# awc_v1.net
KiCad netlist of a schematic drawn in EAGLE
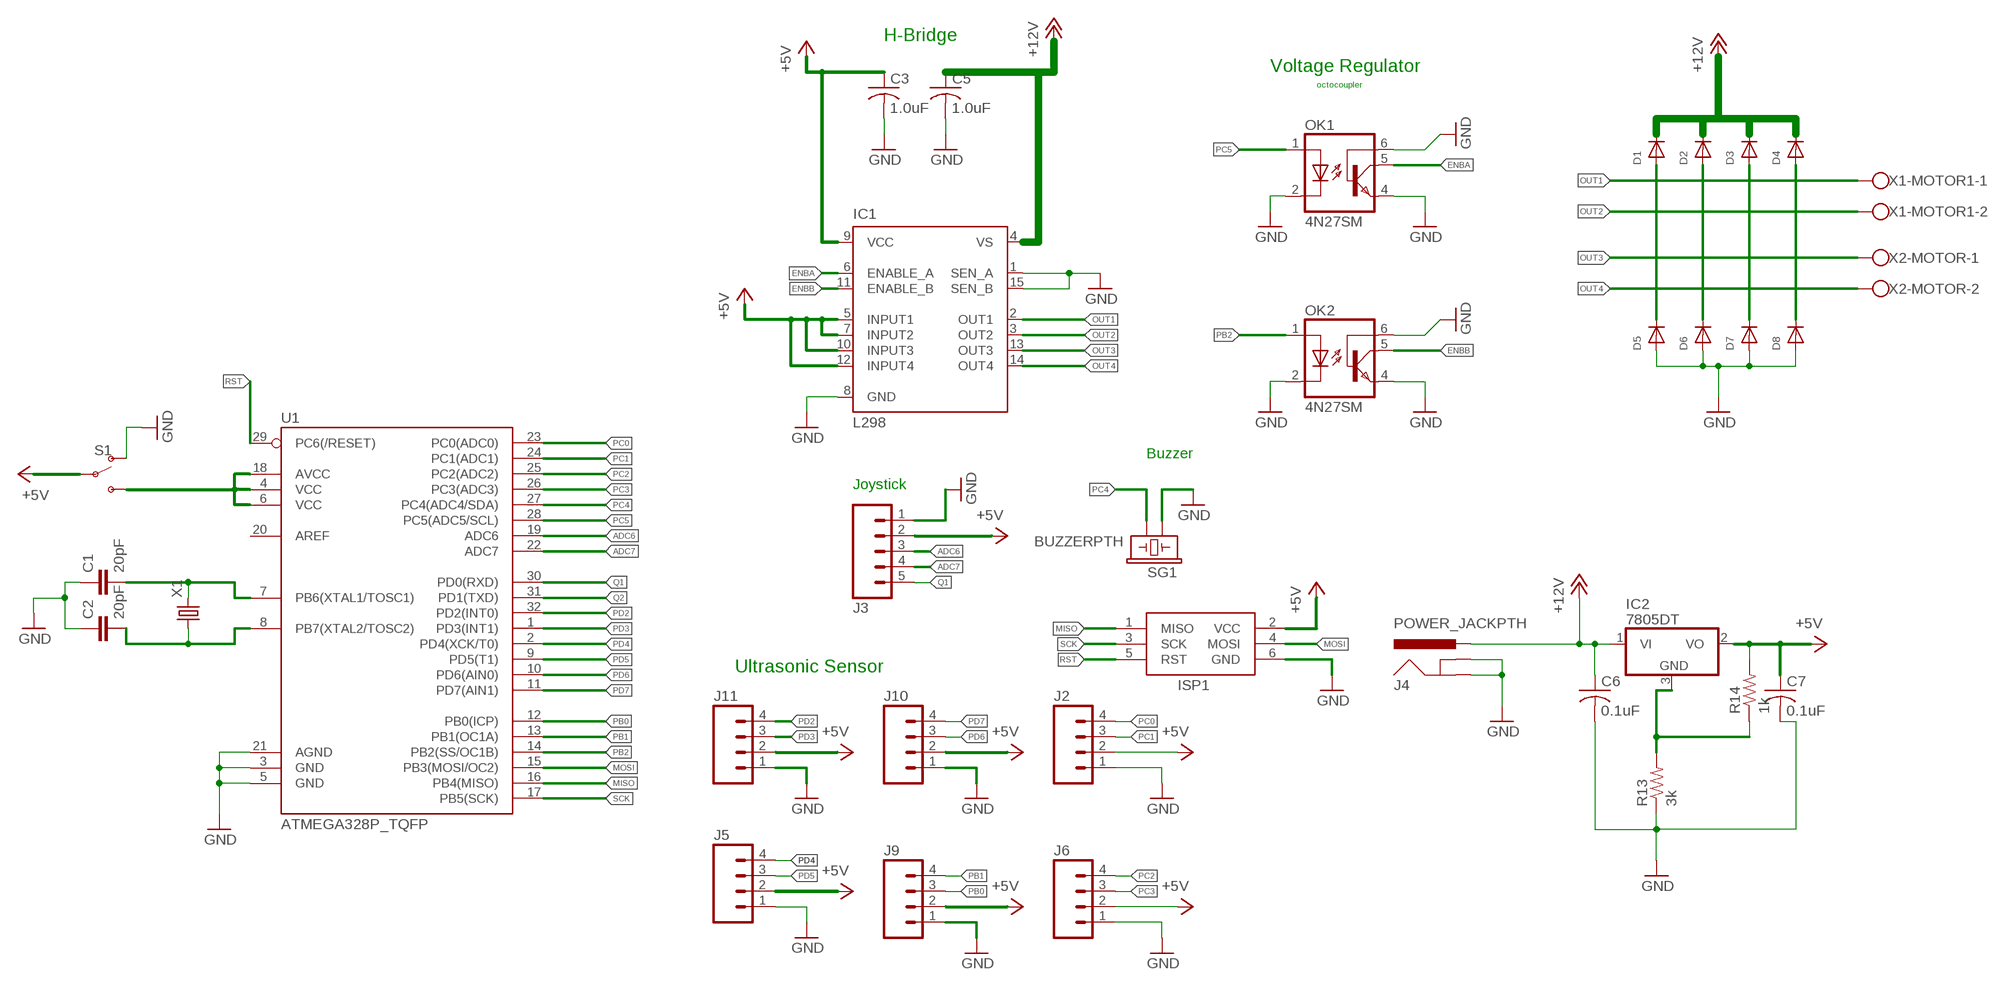
[diagram p0: schematic, sheet 1]

(export (version "E")
  (design (tool "Eeschema 10.0.6"))
  (components
    (comp (ref "C1")
      (value "20pF")
      (footprint "eagle-import:C0805")
      (libsource (lib "eagle-import") (part "C-EUC0805"))
    )
    (comp (ref "C2")
      (value "20pF")
      (footprint "eagle-import:C0805")
      (libsource (lib "eagle-import") (part "C-EUC0805"))
    )
    (comp (ref "C3")
      (value "1.0uF")
      (footprint "eagle-import:C0805")
      (libsource (lib "eagle-import") (part "C-USC0805"))
    )
    (comp (ref "C5")
      (value "1.0uF")
      (footprint "eagle-import:C0805")
      (libsource (lib "eagle-import") (part "C-USC0805"))
    )
    (comp (ref "C6")
      (value "0.1uF")
      (footprint "eagle-import:C0805")
      (libsource (lib "eagle-import") (part "C-USC0805"))
    )
    (comp (ref "C7")
      (value "0.1uF")
      (footprint "eagle-import:C0805")
      (libsource (lib "eagle-import") (part "C-USC0805"))
    )
    (comp (ref "D1")
      (value "DIODESOD-523")
      (footprint "eagle-import:SOD-523")
      (libsource (lib "eagle-import") (part "DIODESOD-523"))
    )
    (comp (ref "D2")
      (value "DIODESOD-523")
      (footprint "eagle-import:SOD-523")
      (libsource (lib "eagle-import") (part "DIODESOD-523"))
    )
    (comp (ref "D3")
      (value "DIODESOD-523")
      (footprint "eagle-import:SOD-523")
      (libsource (lib "eagle-import") (part "DIODESOD-523"))
    )
    (comp (ref "D4")
      (value "DIODESOD-523")
      (footprint "eagle-import:SOD-523")
      (libsource (lib "eagle-import") (part "DIODESOD-523"))
    )
    (comp (ref "D5")
      (value "DIODESOD-523")
      (footprint "eagle-import:SOD-523")
      (libsource (lib "eagle-import") (part "DIODESOD-523"))
    )
    (comp (ref "D6")
      (value "DIODESOD-523")
      (footprint "eagle-import:SOD-523")
      (libsource (lib "eagle-import") (part "DIODESOD-523"))
    )
    (comp (ref "D7")
      (value "DIODESOD-523")
      (footprint "eagle-import:SOD-523")
      (libsource (lib "eagle-import") (part "DIODESOD-523"))
    )
    (comp (ref "D8")
      (value "DIODESOD-523")
      (footprint "eagle-import:SOD-523")
      (libsource (lib "eagle-import") (part "DIODESOD-523"))
    )
    (comp (ref "IC1")
      (value "L298")
      (footprint "eagle-import:MULTIWATT-15")
      (fields (field (name "MPN") "L298N"))
      (libsource (lib "eagle-import") (part "L298"))
    )
    (comp (ref "IC2")
      (value "7805DT")
      (footprint "eagle-import:TO252")
      (libsource (lib "eagle-import") (part "78DT05"))
    )
    (comp (ref "ISP1")
      (value "AVRISP-6")
      (footprint "eagle-import:AVRISP")
      (libsource (lib "eagle-import") (part "AVRISP-6"))
    )
    (comp (ref "J2")
      (value "M04SCREW_LOCK")
      (footprint "eagle-import:SCREWTERMINAL-3.5MM-4_LOCK")
      (libsource (lib "eagle-import") (part "M04SCREW_LOCK"))
    )
    (comp (ref "J3")
      (value "M05SCREW")
      (footprint "eagle-import:SCREWTERMINAL-3.5MM-5")
      (libsource (lib "eagle-import") (part "M05SCREW"))
    )
    (comp (ref "J4")
      (value "POWER_JACKPTH")
      (footprint "eagle-import:POWER_JACK_PTH")
      (libsource (lib "eagle-import") (part "POWER_JACKPTH"))
    )
    (comp (ref "J5")
      (value "M04SCREW_LOCK")
      (footprint "eagle-import:SCREWTERMINAL-3.5MM-4_LOCK")
      (libsource (lib "eagle-import") (part "M04SCREW_LOCK"))
    )
    (comp (ref "J6")
      (value "M04SCREW_LOCK")
      (footprint "eagle-import:SCREWTERMINAL-3.5MM-4_LOCK")
      (libsource (lib "eagle-import") (part "M04SCREW_LOCK"))
    )
    (comp (ref "J9")
      (value "M04SCREW_LOCK")
      (footprint "eagle-import:SCREWTERMINAL-3.5MM-4_LOCK")
      (libsource (lib "eagle-import") (part "M04SCREW_LOCK"))
    )
    (comp (ref "J10")
      (value "M04SCREW_LOCK")
      (footprint "eagle-import:SCREWTERMINAL-3.5MM-4_LOCK")
      (libsource (lib "eagle-import") (part "M04SCREW_LOCK"))
    )
    (comp (ref "J11")
      (value "M04SCREW_LOCK")
      (footprint "eagle-import:SCREWTERMINAL-3.5MM-4_LOCK")
      (libsource (lib "eagle-import") (part "M04SCREW_LOCK"))
    )
    (comp (ref "OK1")
      (value "4N27SM")
      (footprint "eagle-import:DIL6-SMD")
      (fields (field (name "MF") "FAIRCHILD SEMICONDUCTOR") (field (name "MPN") "4N27S-M"))
      (libsource (lib "eagle-import") (part "4N?MS27"))
    )
    (comp (ref "OK2")
      (value "4N27SM")
      (footprint "eagle-import:DIL6-SMD")
      (fields (field (name "MF") "FAIRCHILD SEMICONDUCTOR") (field (name "MPN") "4N27S-M"))
      (libsource (lib "eagle-import") (part "4N?MS27"))
    )
    (comp (ref "R13")
      (value "3k")
      (footprint "eagle-import:0402-RES")
      (libsource (lib "eagle-import") (part "RESISTOR0402"))
    )
    (comp (ref "R14")
      (value "1k")
      (footprint "eagle-import:M0805")
      (libsource (lib "eagle-import") (part "R-US_M0805"))
    )
    (comp (ref "S1")
      (value "SWITCH-SPDT-PTH-11.6X4.0MM")
      (footprint "eagle-import:SWITCH_SPDT_PTH_11.6X4.0MM")
      (libsource (lib "eagle-import") (part "SWITCH-SPDT-PTH-11.6X4.0MM"))
    )
    (comp (ref "SG1")
      (value "BUZZERPTH")
      (footprint "eagle-import:BUZZER-12MM")
      (libsource (lib "eagle-import") (part "BUZZERPTH"))
    )
    (comp (ref "U1")
      (value "ATMEGA328P_TQFP")
      (footprint "eagle-import:TQFP32-08")
      (libsource (lib "eagle-import") (part "ATMEGA328P_TQFP"))
    )
    (comp (ref "X1")
      (value "CRYSTALHC49UP")
      (footprint "eagle-import:HC49UP")
      (libsource (lib "eagle-import") (part "CRYSTALHC49UP"))
    )
    (comp (ref "X1-MOTOR1")
      (value "W237-102")
      (footprint "eagle-import:W237-102")
      (fields (field (name "MPN") "237-102"))
      (libsource (lib "eagle-import") (part "W237-102"))
    )
    (comp (ref "X2-MOTOR")
      (value "W237-102")
      (footprint "eagle-import:W237-102")
      (fields (field (name "MPN") "237-102"))
      (libsource (lib "eagle-import") (part "W237-102"))
    )
  )
  (nets
    (net (code "1") (name "+5V") (class "Default")
      (node (ref "C3") (pin "1") (pinfunction "1_1") (pintype "passive"))
      (node (ref "C7") (pin "1") (pinfunction "1_1") (pintype "passive"))
      (node (ref "IC1") (pin "10") (pinfunction "INPUT3_10") (pintype "input"))
      (node (ref "IC1") (pin "12") (pinfunction "INPUT4_12") (pintype "input"))
      (node (ref "IC1") (pin "5") (pinfunction "INPUT1_5") (pintype "input"))
      (node (ref "IC1") (pin "7") (pinfunction "INPUT2_7") (pintype "input"))
      (node (ref "IC1") (pin "9") (pinfunction "VCC_9") (pintype "power_in"))
      (node (ref "IC2") (pin "2") (pinfunction "VO_2") (pintype "passive"))
      (node (ref "ISP1") (pin "2") (pinfunction "VCC_2") (pintype "power_in"))
      (node (ref "J10") (pin "2") (pinfunction "2_2") (pintype "passive"))
      (node (ref "J11") (pin "2") (pinfunction "2_2") (pintype "passive"))
      (node (ref "J2") (pin "2") (pinfunction "2_2") (pintype "passive"))
      (node (ref "J3") (pin "2") (pinfunction "2_2") (pintype "passive"))
      (node (ref "J5") (pin "2") (pinfunction "2_2") (pintype "passive"))
      (node (ref "J6") (pin "2") (pinfunction "2_2") (pintype "passive"))
      (node (ref "J9") (pin "2") (pinfunction "2_2") (pintype "passive"))
      (node (ref "R14") (pin "2") (pinfunction "2_2") (pintype "passive"))
      (node (ref "S1") (pin "2") (pinfunction "P_2") (pintype "passive"))
    )
    (net (code "2") (name "+12V") (class "Default")
      (node (ref "C5") (pin "1") (pinfunction "1_1") (pintype "passive"))
      (node (ref "C6") (pin "1") (pinfunction "1_1") (pintype "passive"))
      (node (ref "D1") (pin "K") (pinfunction "C_K") (pintype "passive"))
      (node (ref "D2") (pin "K") (pinfunction "C_K") (pintype "passive"))
      (node (ref "D3") (pin "K") (pinfunction "C_K") (pintype "passive"))
      (node (ref "D4") (pin "K") (pinfunction "C_K") (pintype "passive"))
      (node (ref "IC1") (pin "4") (pinfunction "VS_4") (pintype "power_in"))
      (node (ref "IC2") (pin "1") (pinfunction "VI_1") (pintype "input"))
      (node (ref "J4") (pin "PWR") (pinfunction "PWR_PWR") (pintype "bidirectional"))
    )
    (net (code "3") (name "ADC6") (class "Default")
      (node (ref "J3") (pin "3") (pinfunction "3_3") (pintype "passive"))
      (node (ref "U1") (pin "19") (pinfunction "ADC6_19") (pintype "bidirectional"))
    )
    (net (code "4") (name "ADC7") (class "Default")
      (node (ref "J3") (pin "4") (pinfunction "4_4") (pintype "passive"))
      (node (ref "U1") (pin "22") (pinfunction "ADC7_22") (pintype "bidirectional"))
    )
    (net (code "5") (name "ENBA") (class "Default")
      (node (ref "IC1") (pin "6") (pinfunction "ENABLE_A_6") (pintype "input"))
      (node (ref "OK1") (pin "5") (pinfunction "COL_5") (pintype "passive"))
    )
    (net (code "6") (name "ENBB") (class "Default")
      (node (ref "IC1") (pin "11") (pinfunction "ENABLE_B_11") (pintype "input"))
      (node (ref "OK2") (pin "5") (pinfunction "COL_5") (pintype "passive"))
    )
    (net (code "7") (name "GND") (class "Default")
      (node (ref "C1") (pin "1") (pinfunction "1_1") (pintype "passive"))
      (node (ref "C2") (pin "1") (pinfunction "1_1") (pintype "passive"))
      (node (ref "C3") (pin "2") (pinfunction "2_2") (pintype "passive"))
      (node (ref "C5") (pin "2") (pinfunction "2_2") (pintype "passive"))
      (node (ref "C6") (pin "2") (pinfunction "2_2") (pintype "passive"))
      (node (ref "C7") (pin "2") (pinfunction "2_2") (pintype "passive"))
      (node (ref "D5") (pin "A") (pinfunction "A_A") (pintype "passive"))
      (node (ref "D6") (pin "A") (pinfunction "A_A") (pintype "passive"))
      (node (ref "D7") (pin "A") (pinfunction "A_A") (pintype "passive"))
      (node (ref "D8") (pin "A") (pinfunction "A_A") (pintype "passive"))
      (node (ref "IC1") (pin "1") (pinfunction "SEN_A_1") (pintype "input"))
      (node (ref "IC1") (pin "15") (pinfunction "SEN_B_15") (pintype "input"))
      (node (ref "IC1") (pin "8") (pinfunction "GND_8") (pintype "power_in"))
      (node (ref "ISP1") (pin "6") (pinfunction "GND_6") (pintype "power_in"))
      (node (ref "J10") (pin "1") (pinfunction "1_1") (pintype "passive"))
      (node (ref "J11") (pin "1") (pinfunction "1_1") (pintype "passive"))
      (node (ref "J2") (pin "1") (pinfunction "1_1") (pintype "passive"))
      (node (ref "J3") (pin "1") (pinfunction "1_1") (pintype "passive"))
      (node (ref "J4") (pin "GND") (pinfunction "GND_GND") (pintype "bidirectional"))
      (node (ref "J4") (pin "GNDBREAK") (pinfunction "GNDBREAK_GNDBREAK") (pintype "bidirectional"))
      (node (ref "J5") (pin "1") (pinfunction "1_1") (pintype "passive"))
      (node (ref "J6") (pin "1") (pinfunction "1_1") (pintype "passive"))
      (node (ref "J9") (pin "1") (pinfunction "1_1") (pintype "passive"))
      (node (ref "OK1") (pin "2") (pinfunction "C_2") (pintype "passive"))
      (node (ref "OK1") (pin "4") (pinfunction "EMI_4") (pintype "passive"))
      (node (ref "OK1") (pin "6") (pinfunction "BAS_6") (pintype "passive"))
      (node (ref "OK2") (pin "2") (pinfunction "C_2") (pintype "passive"))
      (node (ref "OK2") (pin "4") (pinfunction "EMI_4") (pintype "passive"))
      (node (ref "OK2") (pin "6") (pinfunction "BAS_6") (pintype "passive"))
      (node (ref "R13") (pin "1") (pinfunction "1_1") (pintype "passive"))
      (node (ref "S1") (pin "1") (pinfunction "O_1") (pintype "passive"))
      (node (ref "SG1") (pin "+") (pinfunction "1_+") (pintype "passive"))
      (node (ref "U1") (pin "21") (pinfunction "AGND_21") (pintype "bidirectional"))
      (node (ref "U1") (pin "3") (pinfunction "GND_3") (pintype "bidirectional"))
      (node (ref "U1") (pin "5") (pinfunction "GND_5") (pintype "bidirectional"))
    )
    (net (code "8") (name "MISO") (class "Default")
      (node (ref "ISP1") (pin "1") (pinfunction "MISO_1") (pintype "input"))
      (node (ref "U1") (pin "16") (pinfunction "PB4(MISO)_16") (pintype "bidirectional"))
    )
    (net (code "9") (name "MOSI") (class "Default")
      (node (ref "ISP1") (pin "4") (pinfunction "MOSI_4") (pintype "output"))
      (node (ref "U1") (pin "15") (pinfunction "PB3(MOSI/OC2)_15") (pintype "bidirectional"))
    )
    (net (code "10") (name "Net-(D5-C)") (class "Default")
      (node (ref "D1") (pin "A") (pinfunction "A_A") (pintype "passive"))
      (node (ref "D5") (pin "K") (pinfunction "C_K") (pintype "passive"))
    )
    (net (code "11") (name "Net-(D6-C)") (class "Default")
      (node (ref "D2") (pin "A") (pinfunction "A_A") (pintype "passive"))
      (node (ref "D6") (pin "K") (pinfunction "C_K") (pintype "passive"))
    )
    (net (code "12") (name "Net-(D7-C)") (class "Default")
      (node (ref "D3") (pin "A") (pinfunction "A_A") (pintype "passive"))
      (node (ref "D7") (pin "K") (pinfunction "C_K") (pintype "passive"))
    )
    (net (code "13") (name "Net-(D8-C)") (class "Default")
      (node (ref "D4") (pin "A") (pinfunction "A_A") (pintype "passive"))
      (node (ref "D8") (pin "K") (pinfunction "C_K") (pintype "passive"))
    )
    (net (code "14") (name "Net-(IC2-GND)") (class "Default")
      (node (ref "IC2") (pin "3") (pinfunction "GND_3") (pintype "passive"))
      (node (ref "R13") (pin "2") (pinfunction "2_2") (pintype "passive"))
      (node (ref "R14") (pin "1") (pinfunction "1_1") (pintype "passive"))
    )
    (net (code "15") (name "Net-(S1-S)") (class "Default")
      (node (ref "S1") (pin "3") (pinfunction "S_3") (pintype "passive"))
      (node (ref "U1") (pin "18") (pinfunction "AVCC_18") (pintype "bidirectional"))
      (node (ref "U1") (pin "4") (pinfunction "VCC_4") (pintype "bidirectional"))
      (node (ref "U1") (pin "6") (pinfunction "VCC_6") (pintype "bidirectional"))
    )
    (net (code "16") (name "Net-(U1-PB6(XTAL1{slash}TOSC1))") (class "Default")
      (node (ref "C1") (pin "2") (pinfunction "2_2") (pintype "passive"))
      (node (ref "U1") (pin "7") (pinfunction "PB6(XTAL1/TOSC1)_7") (pintype "bidirectional"))
      (node (ref "X1") (pin "2") (pinfunction "2_2") (pintype "passive"))
    )
    (net (code "17") (name "Net-(U1-PB7(XTAL2{slash}TOSC2))") (class "Default")
      (node (ref "C2") (pin "2") (pinfunction "2_2") (pintype "passive"))
      (node (ref "U1") (pin "8") (pinfunction "PB7(XTAL2/TOSC2)_8") (pintype "bidirectional"))
      (node (ref "X1") (pin "1") (pinfunction "1_1") (pintype "passive"))
    )
    (net (code "18") (name "OUT1") (class "Default")
      (node (ref "IC1") (pin "2") (pinfunction "OUT1_2") (pintype "output"))
      (node (ref "X1-MOTOR1") (pin "1") (pinfunction "KL_1") (pintype "passive"))
    )
    (net (code "19") (name "OUT2") (class "Default")
      (node (ref "IC1") (pin "3") (pinfunction "OUT2_3") (pintype "output"))
      (node (ref "X1-MOTOR1") (pin "2") (pinfunction "KL_2") (pintype "passive"))
    )
    (net (code "20") (name "OUT3") (class "Default")
      (node (ref "IC1") (pin "13") (pinfunction "OUT3_13") (pintype "output"))
      (node (ref "X2-MOTOR") (pin "1") (pinfunction "KL_1") (pintype "passive"))
    )
    (net (code "21") (name "OUT4") (class "Default")
      (node (ref "IC1") (pin "14") (pinfunction "OUT4_14") (pintype "output"))
      (node (ref "X2-MOTOR") (pin "2") (pinfunction "KL_2") (pintype "passive"))
    )
    (net (code "22") (name "PB0") (class "Default")
      (node (ref "J9") (pin "3") (pinfunction "3_3") (pintype "passive"))
      (node (ref "U1") (pin "12") (pinfunction "PB0(ICP)_12") (pintype "bidirectional"))
    )
    (net (code "23") (name "PB1") (class "Default")
      (node (ref "J9") (pin "4") (pinfunction "4_4") (pintype "passive"))
      (node (ref "U1") (pin "13") (pinfunction "PB1(OC1A)_13") (pintype "bidirectional"))
    )
    (net (code "24") (name "PB2") (class "Default")
      (node (ref "OK2") (pin "1") (pinfunction "A_1") (pintype "passive"))
      (node (ref "U1") (pin "14") (pinfunction "PB2(SS/OC1B)_14") (pintype "bidirectional"))
    )
    (net (code "25") (name "PC0") (class "Default")
      (node (ref "J2") (pin "4") (pinfunction "4_4") (pintype "passive"))
      (node (ref "U1") (pin "23") (pinfunction "PC0(ADC0)_23") (pintype "bidirectional"))
    )
    (net (code "26") (name "PC1") (class "Default")
      (node (ref "J2") (pin "3") (pinfunction "3_3") (pintype "passive"))
      (node (ref "U1") (pin "24") (pinfunction "PC1(ADC1)_24") (pintype "bidirectional"))
    )
    (net (code "27") (name "PC2") (class "Default")
      (node (ref "J6") (pin "4") (pinfunction "4_4") (pintype "passive"))
      (node (ref "U1") (pin "25") (pinfunction "PC2(ADC2)_25") (pintype "bidirectional"))
    )
    (net (code "28") (name "PC3") (class "Default")
      (node (ref "J6") (pin "3") (pinfunction "3_3") (pintype "passive"))
      (node (ref "U1") (pin "26") (pinfunction "PC3(ADC3)_26") (pintype "bidirectional"))
    )
    (net (code "29") (name "PC4") (class "Default")
      (node (ref "SG1") (pin "-") (pinfunction "2_-") (pintype "passive"))
      (node (ref "U1") (pin "27") (pinfunction "PC4(ADC4/SDA)_27") (pintype "bidirectional"))
    )
    (net (code "30") (name "PC5") (class "Default")
      (node (ref "OK1") (pin "1") (pinfunction "A_1") (pintype "passive"))
      (node (ref "U1") (pin "28") (pinfunction "PC5(ADC5/SCL)_28") (pintype "bidirectional"))
    )
    (net (code "31") (name "PD2") (class "Default")
      (node (ref "J11") (pin "4") (pinfunction "4_4") (pintype "passive"))
      (node (ref "U1") (pin "32") (pinfunction "PD2(INT0)_32") (pintype "bidirectional"))
    )
    (net (code "32") (name "PD3") (class "Default")
      (node (ref "J11") (pin "3") (pinfunction "3_3") (pintype "passive"))
      (node (ref "U1") (pin "1") (pinfunction "PD3(INT1)_1") (pintype "bidirectional"))
    )
    (net (code "33") (name "PD4") (class "Default")
      (node (ref "J5") (pin "4") (pinfunction "4_4") (pintype "passive"))
      (node (ref "U1") (pin "2") (pinfunction "PD4(XCK/T0)_2") (pintype "bidirectional"))
    )
    (net (code "34") (name "PD5") (class "Default")
      (node (ref "J5") (pin "3") (pinfunction "3_3") (pintype "passive"))
      (node (ref "U1") (pin "9") (pinfunction "PD5(T1)_9") (pintype "bidirectional"))
    )
    (net (code "35") (name "PD6") (class "Default")
      (node (ref "J10") (pin "3") (pinfunction "3_3") (pintype "passive"))
      (node (ref "U1") (pin "10") (pinfunction "PD6(AIN0)_10") (pintype "bidirectional"))
    )
    (net (code "36") (name "PD7") (class "Default")
      (node (ref "J10") (pin "4") (pinfunction "4_4") (pintype "passive"))
      (node (ref "U1") (pin "11") (pinfunction "PD7(AIN1)_11") (pintype "bidirectional"))
    )
    (net (code "37") (name "Q1") (class "Default")
      (node (ref "J3") (pin "5") (pinfunction "5_5") (pintype "passive"))
      (node (ref "U1") (pin "30") (pinfunction "PD0(RXD)_30") (pintype "bidirectional"))
    )
    (net (code "38") (name "Q2") (class "Default")
      (node (ref "U1") (pin "31") (pinfunction "PD1(TXD)_31") (pintype "bidirectional"))
    )
    (net (code "39") (name "RST") (class "Default")
      (node (ref "ISP1") (pin "5") (pinfunction "RST_5") (pintype "output"))
      (node (ref "U1") (pin "29") (pinfunction "PC6(/RESET)_29") (pintype "bidirectional"))
    )
    (net (code "40") (name "SCK") (class "Default")
      (node (ref "ISP1") (pin "3") (pinfunction "SCK_3") (pintype "output"))
      (node (ref "U1") (pin "17") (pinfunction "PB5(SCK)_17") (pintype "bidirectional"))
    )
    (net (code "41") (name "unconnected-(U1-AREF-Pad20)") (class "Default")
      (node (ref "U1") (pin "20") (pinfunction "AREF_20") (pintype "bidirectional"))
    )
  )
)
